# moire_v1_4-bwip.net
KiCad netlist of a schematic drawn in EAGLE
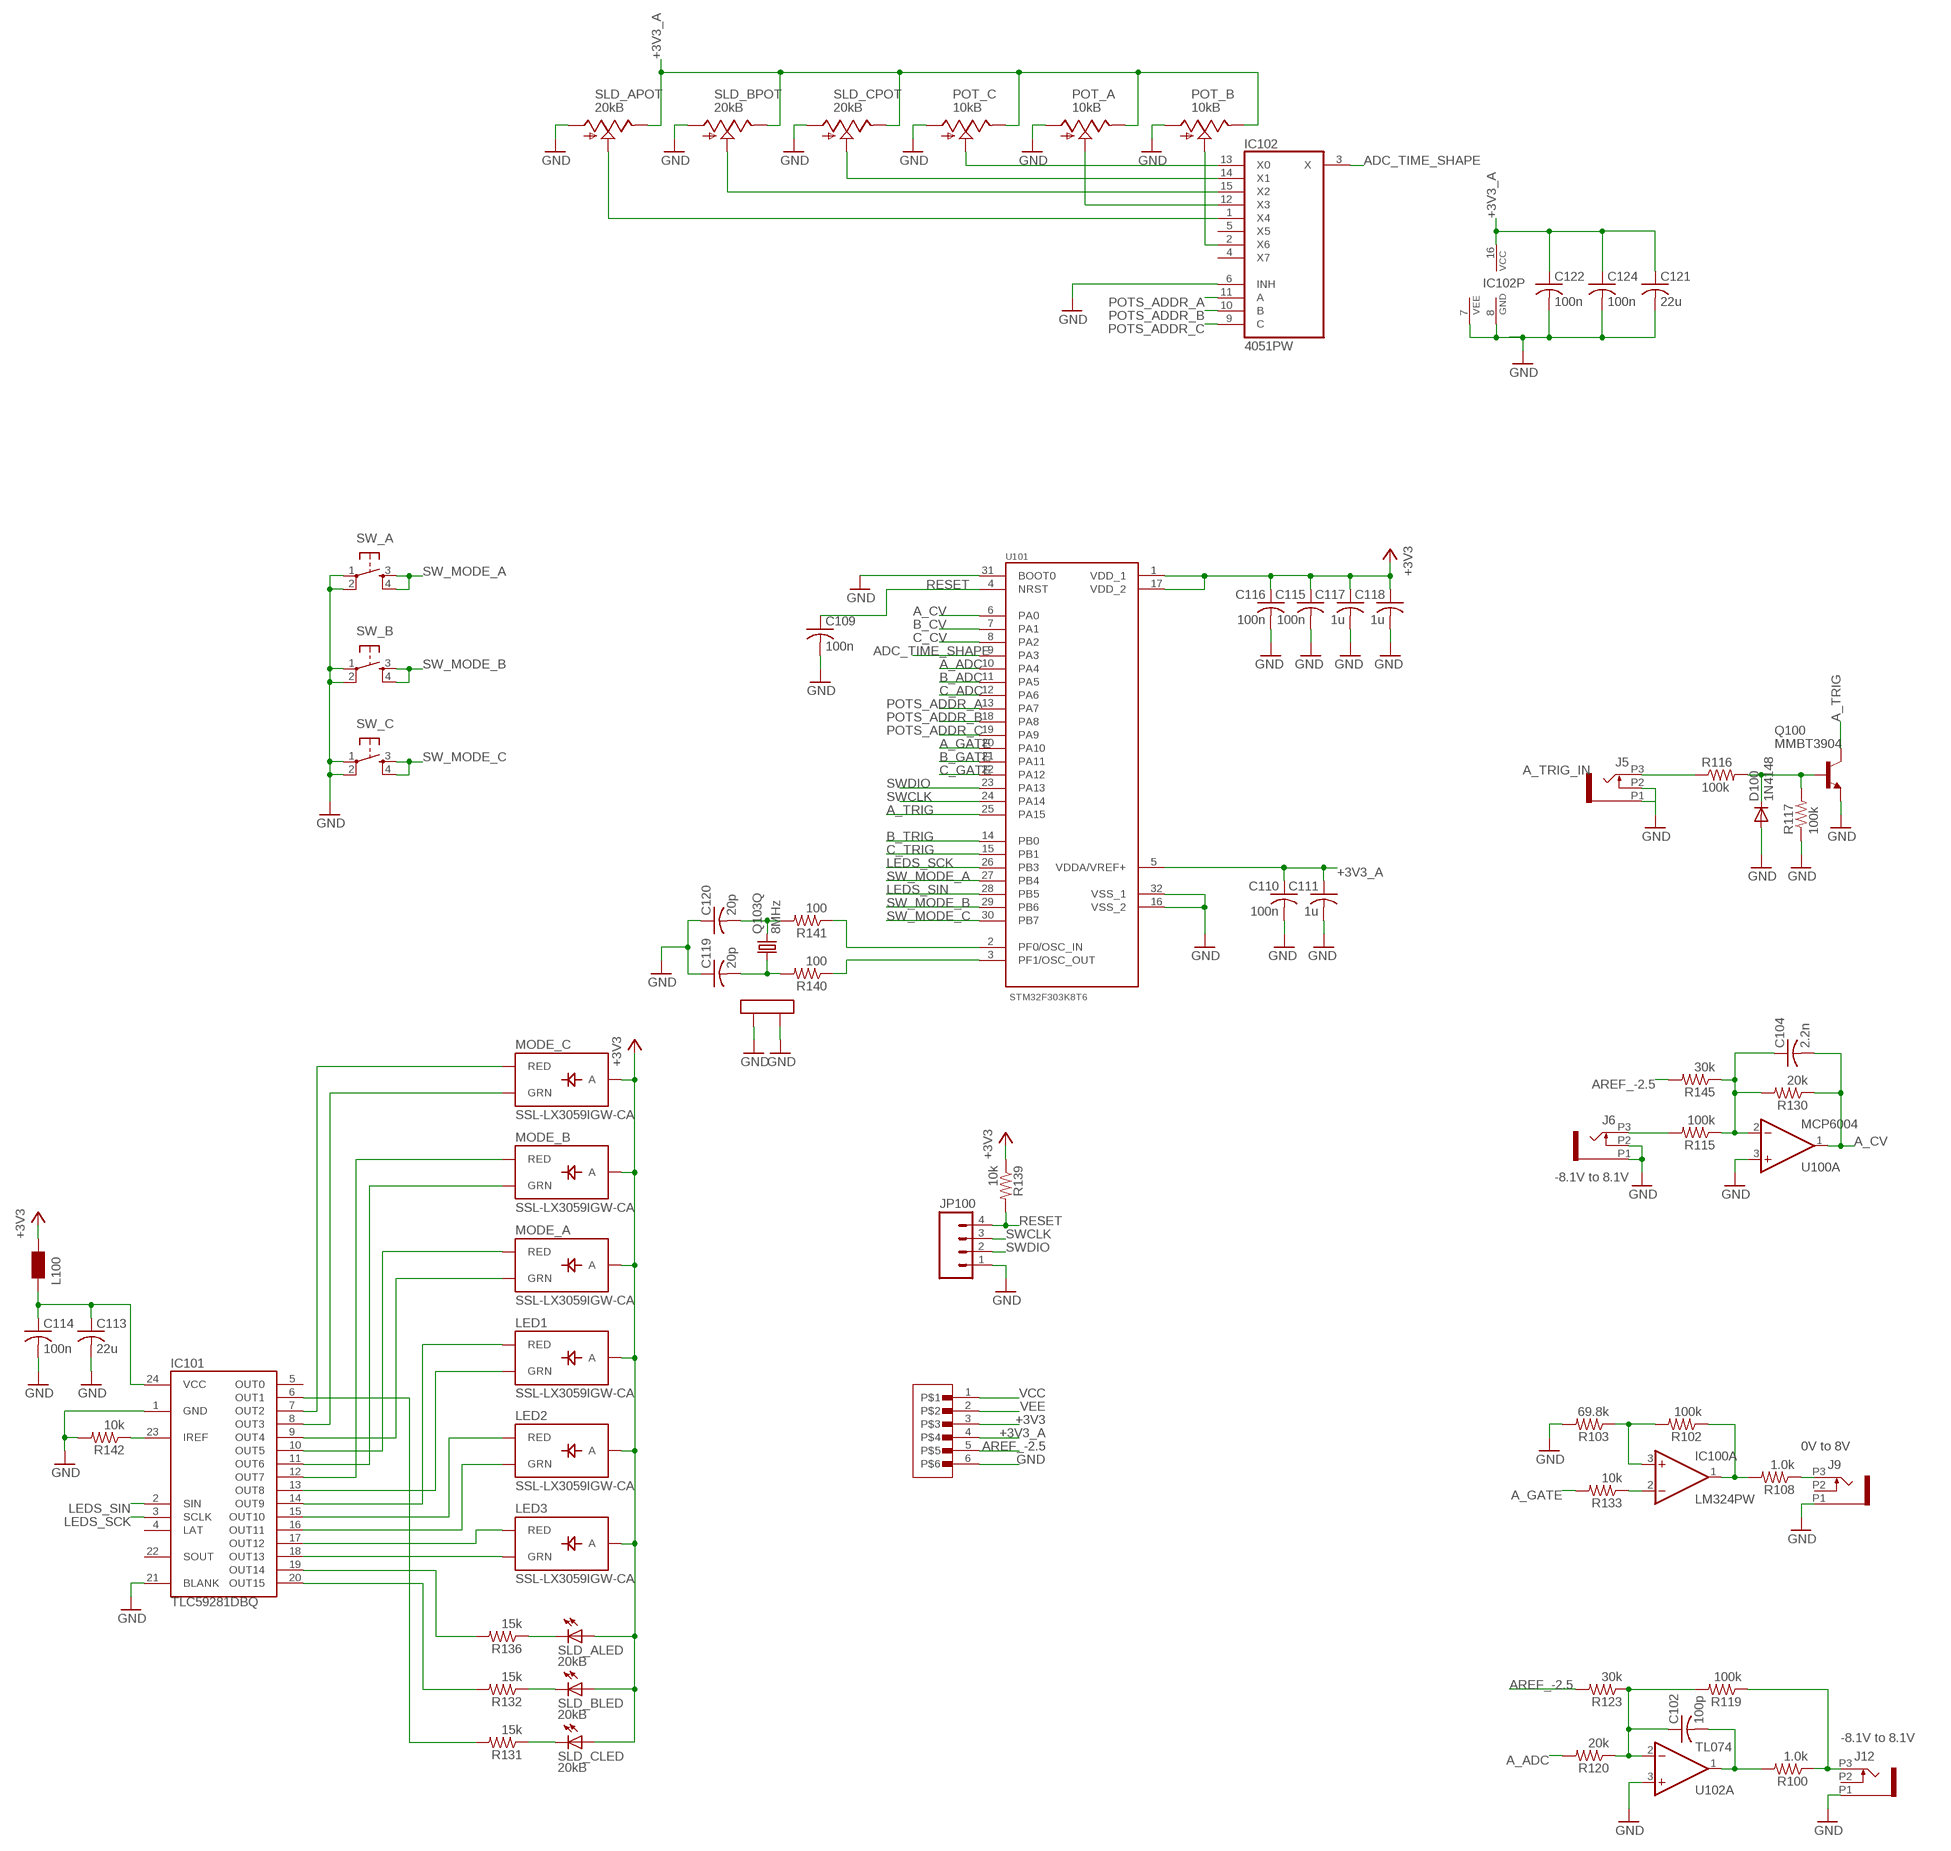
[diagram p0: schematic, sheet 1, part 1 of 2]
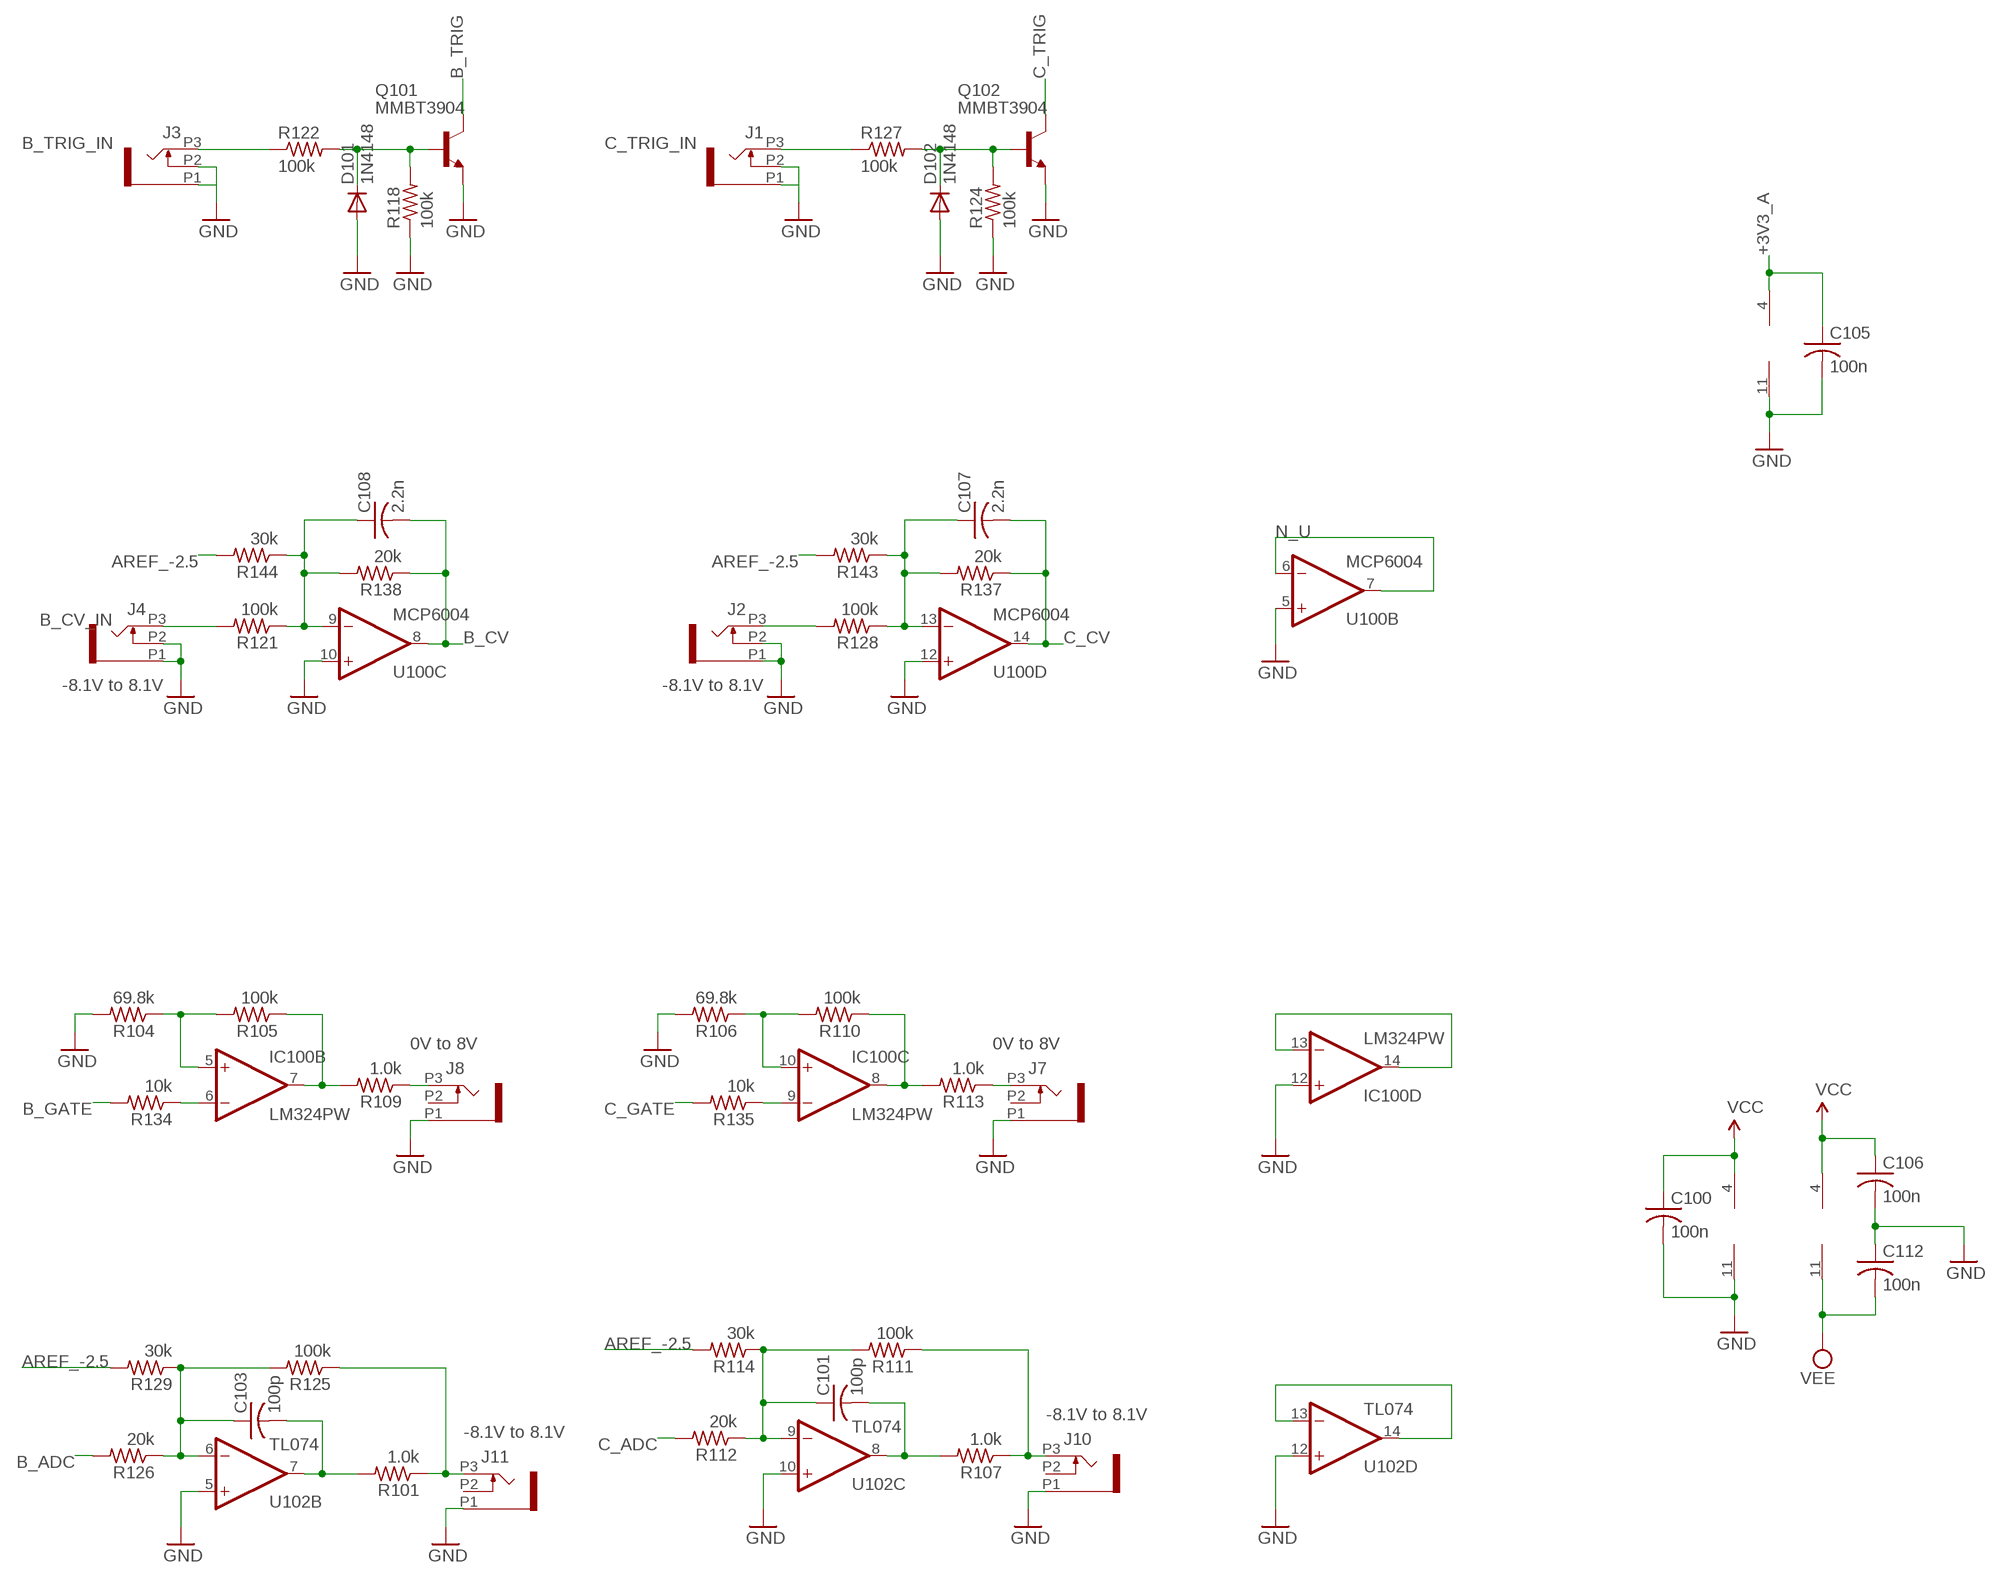
[diagram p1: schematic, sheet 1, part 2 of 2]
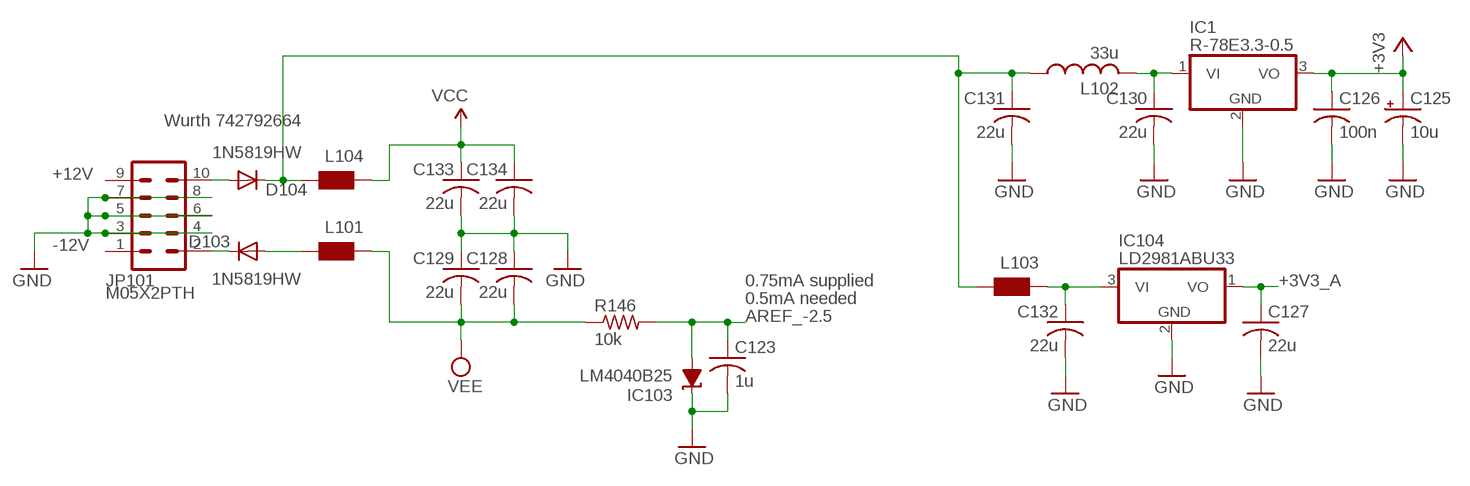
[diagram p2: schematic, sheet 2]

(export (version "E")
  (design (tool "Eeschema 10.0.6"))
  (components
    (comp (ref "C100")
      (value "100n")
      (footprint "eagle-import:C0603")
      (libsource (lib "eagle-import") (part "C-USC0603"))
    )
    (comp (ref "C101")
      (value "100p")
      (footprint "eagle-import:C0603")
      (libsource (lib "eagle-import") (part "C-USC0603"))
    )
    (comp (ref "C102")
      (value "100p")
      (footprint "eagle-import:C0603")
      (libsource (lib "eagle-import") (part "C-USC0603"))
    )
    (comp (ref "C103")
      (value "100p")
      (footprint "eagle-import:C0603")
      (libsource (lib "eagle-import") (part "C-USC0603"))
    )
    (comp (ref "C104")
      (value "2.2n")
      (footprint "eagle-import:C0603")
      (libsource (lib "eagle-import") (part "C-USC0603"))
    )
    (comp (ref "C105")
      (value "100n")
      (footprint "eagle-import:C0603")
      (libsource (lib "eagle-import") (part "C-USC0603"))
    )
    (comp (ref "C106")
      (value "100n")
      (footprint "eagle-import:C0603")
      (libsource (lib "eagle-import") (part "C-USC0603"))
    )
    (comp (ref "C107")
      (value "2.2n")
      (footprint "eagle-import:C0603")
      (libsource (lib "eagle-import") (part "C-USC0603"))
    )
    (comp (ref "C108")
      (value "2.2n")
      (footprint "eagle-import:C0603")
      (libsource (lib "eagle-import") (part "C-USC0603"))
    )
    (comp (ref "C109")
      (value "100n")
      (footprint "eagle-import:C0603")
      (libsource (lib "eagle-import") (part "C-USC0603"))
    )
    (comp (ref "C110")
      (value "100n")
      (footprint "eagle-import:C0603")
      (libsource (lib "eagle-import") (part "C-USC0603"))
    )
    (comp (ref "C111")
      (value "1u")
      (footprint "eagle-import:C0603")
      (libsource (lib "eagle-import") (part "C-USC0603"))
    )
    (comp (ref "C112")
      (value "100n")
      (footprint "eagle-import:C0603")
      (libsource (lib "eagle-import") (part "C-USC0603"))
    )
    (comp (ref "C113")
      (value "22u")
      (footprint "eagle-import:C1206")
      (libsource (lib "eagle-import") (part "C-USC1206"))
    )
    (comp (ref "C114")
      (value "100n")
      (footprint "eagle-import:C0603")
      (libsource (lib "eagle-import") (part "C-USC0603"))
    )
    (comp (ref "C115")
      (value "100n")
      (footprint "eagle-import:C0603")
      (libsource (lib "eagle-import") (part "C-USC0603"))
    )
    (comp (ref "C116")
      (value "100n")
      (footprint "eagle-import:C0603")
      (libsource (lib "eagle-import") (part "C-USC0603"))
    )
    (comp (ref "C117")
      (value "1u")
      (footprint "eagle-import:C0603")
      (libsource (lib "eagle-import") (part "C-USC0603"))
    )
    (comp (ref "C118")
      (value "1u")
      (footprint "eagle-import:C0603")
      (libsource (lib "eagle-import") (part "C-USC0603"))
    )
    (comp (ref "C119")
      (value "20p")
      (footprint "eagle-import:C0603")
      (libsource (lib "eagle-import") (part "C-USC0603"))
    )
    (comp (ref "C120")
      (value "20p")
      (footprint "eagle-import:C0603")
      (libsource (lib "eagle-import") (part "C-USC0603"))
    )
    (comp (ref "C121")
      (value "22u")
      (footprint "eagle-import:C1206")
      (libsource (lib "eagle-import") (part "C-USC1206"))
    )
    (comp (ref "C122")
      (value "100n")
      (footprint "eagle-import:C0603")
      (libsource (lib "eagle-import") (part "C-USC0603"))
    )
    (comp (ref "C124")
      (value "100n")
      (footprint "eagle-import:C0603")
      (libsource (lib "eagle-import") (part "C-USC0603"))
    )
    (comp (ref "D100")
      (value "1N4148")
      (footprint "eagle-import:SOD523")
      (libsource (lib "eagle-import") (part "DIODE-SOD523"))
    )
    (comp (ref "D101")
      (value "1N4148")
      (footprint "eagle-import:SOD523")
      (libsource (lib "eagle-import") (part "DIODE-SOD523"))
    )
    (comp (ref "D102")
      (value "1N4148")
      (footprint "eagle-import:SOD523")
      (libsource (lib "eagle-import") (part "DIODE-SOD523"))
    )
    (comp (ref "IC100")
      (value "LM324PW")
      (footprint "eagle-import:TSSOP14_065")
      (libsource (lib "eagle-import") (part "TL074PW"))
    )
    (comp (ref "IC101")
      (value "TLC59281DBQ")
      (footprint "eagle-import:TSSOP24_0635")
      (libsource (lib "eagle-import") (part "TLC59281DBQ"))
    )
    (comp (ref "IC102")
      (value "4051PW")
      (footprint "eagle-import:TSSOP16_065")
      (libsource (lib "eagle-import") (part "4051PW"))
    )
    (comp (ref "J1")
      (value "PJ301_THONKICONN6")
      (footprint "eagle-import:WQP_PJ_301M6")
      (libsource (lib "eagle-import") (part "PJ301_THONKICONN6"))
    )
    (comp (ref "J2")
      (value "PJ301_THONKICONN6")
      (footprint "eagle-import:WQP_PJ_301M6")
      (libsource (lib "eagle-import") (part "PJ301_THONKICONN6"))
    )
    (comp (ref "J3")
      (value "PJ301_THONKICONN6")
      (footprint "eagle-import:WQP_PJ_301M6")
      (libsource (lib "eagle-import") (part "PJ301_THONKICONN6"))
    )
    (comp (ref "J4")
      (value "PJ301_THONKICONN6")
      (footprint "eagle-import:WQP_PJ_301M6")
      (libsource (lib "eagle-import") (part "PJ301_THONKICONN6"))
    )
    (comp (ref "J5")
      (value "PJ301_THONKICONN6")
      (footprint "eagle-import:WQP_PJ_301M6")
      (libsource (lib "eagle-import") (part "PJ301_THONKICONN6"))
    )
    (comp (ref "J6")
      (value "PJ301_THONKICONN6")
      (footprint "eagle-import:WQP_PJ_301M6")
      (libsource (lib "eagle-import") (part "PJ301_THONKICONN6"))
    )
    (comp (ref "J7")
      (value "PJ301_THONKICONN6")
      (footprint "eagle-import:WQP_PJ_301M6")
      (libsource (lib "eagle-import") (part "PJ301_THONKICONN6"))
    )
    (comp (ref "J8")
      (value "PJ301_THONKICONN6")
      (footprint "eagle-import:WQP_PJ_301M6")
      (libsource (lib "eagle-import") (part "PJ301_THONKICONN6"))
    )
    (comp (ref "J9")
      (value "PJ301_THONKICONN6")
      (footprint "eagle-import:WQP_PJ_301M6")
      (libsource (lib "eagle-import") (part "PJ301_THONKICONN6"))
    )
    (comp (ref "J10")
      (value "PJ301_THONKICONN6")
      (footprint "eagle-import:WQP_PJ_301M6")
      (libsource (lib "eagle-import") (part "PJ301_THONKICONN6"))
    )
    (comp (ref "J11")
      (value "PJ301_THONKICONN6")
      (footprint "eagle-import:WQP_PJ_301M6")
      (libsource (lib "eagle-import") (part "PJ301_THONKICONN6"))
    )
    (comp (ref "J12")
      (value "PJ301_THONKICONN6")
      (footprint "eagle-import:WQP_PJ_301M6")
      (libsource (lib "eagle-import") (part "PJ301_THONKICONN6"))
    )
    (comp (ref "JP100")
      (value "M04PTH")
      (footprint "eagle-import:1X04")
      (libsource (lib "eagle-import") (part "M04PTH"))
    )
    (comp (ref "L100")
      (value "WE-CBF_0603")
      (footprint "eagle-import:0603")
      (libsource (lib "eagle-import") (part "WE-CBF_0603"))
    )
    (comp (ref "LED1")
      (value "SSL-LX3059IGW-CA")
      (footprint "eagle-import:LED-BICOLOR-THROUGHHOLE-LUMEX")
      (libsource (lib "eagle-import") (part "LED-BICOLOR-THROUGHHOLE-CA"))
    )
    (comp (ref "LED2")
      (value "SSL-LX3059IGW-CA")
      (footprint "eagle-import:LED-BICOLOR-THROUGHHOLE-LUMEX")
      (libsource (lib "eagle-import") (part "LED-BICOLOR-THROUGHHOLE-CA"))
    )
    (comp (ref "LED3")
      (value "SSL-LX3059IGW-CA")
      (footprint "eagle-import:LED-BICOLOR-THROUGHHOLE-LUMEX")
      (libsource (lib "eagle-import") (part "LED-BICOLOR-THROUGHHOLE-CA"))
    )
    (comp (ref "MODE_A")
      (value "SSL-LX3059IGW-CA")
      (footprint "eagle-import:LED-BICOLOR-THROUGHHOLE-LUMEX")
      (libsource (lib "eagle-import") (part "LED-BICOLOR-THROUGHHOLE-CA"))
    )
    (comp (ref "MODE_B")
      (value "SSL-LX3059IGW-CA")
      (footprint "eagle-import:LED-BICOLOR-THROUGHHOLE-LUMEX")
      (libsource (lib "eagle-import") (part "LED-BICOLOR-THROUGHHOLE-CA"))
    )
    (comp (ref "MODE_C")
      (value "SSL-LX3059IGW-CA")
      (footprint "eagle-import:LED-BICOLOR-THROUGHHOLE-LUMEX")
      (libsource (lib "eagle-import") (part "LED-BICOLOR-THROUGHHOLE-CA"))
    )
    (comp (ref "POT_A")
      (value "10kB")
      (footprint "eagle-import:ALPS_POT_VERTICAL")
      (libsource (lib "eagle-import") (part "POT_USVERTICAL"))
    )
    (comp (ref "POT_B")
      (value "10kB")
      (footprint "eagle-import:ALPS_POT_VERTICAL")
      (libsource (lib "eagle-import") (part "POT_USVERTICAL"))
    )
    (comp (ref "POT_C")
      (value "10kB")
      (footprint "eagle-import:ALPS_POT_VERTICAL")
      (libsource (lib "eagle-import") (part "POT_USVERTICAL"))
    )
    (comp (ref "Q100")
      (value "MMBT3904")
      (footprint "eagle-import:SOT23-BEC")
      (libsource (lib "eagle-import") (part "-NPN-SOT23-BECMMBT3904LT1"))
    )
    (comp (ref "Q101")
      (value "MMBT3904")
      (footprint "eagle-import:SOT23-BEC")
      (libsource (lib "eagle-import") (part "-NPN-SOT23-BECMMBT3904LT1"))
    )
    (comp (ref "Q102")
      (value "MMBT3904")
      (footprint "eagle-import:SOT23-BEC")
      (libsource (lib "eagle-import") (part "-NPN-SOT23-BECMMBT3904LT1"))
    )
    (comp (ref "Q103")
      (value "8MHz")
      (footprint "eagle-import:CTS406")
      (libsource (lib "eagle-import") (part "CRYSTAL"))
    )
    (comp (ref "R100")
      (value "1.0k")
      (footprint "eagle-import:R0603")
      (libsource (lib "eagle-import") (part "R-US_R0603"))
    )
    (comp (ref "R101")
      (value "1.0k")
      (footprint "eagle-import:R0603")
      (libsource (lib "eagle-import") (part "R-US_R0603"))
    )
    (comp (ref "R102")
      (value "100k")
      (footprint "eagle-import:R0603")
      (libsource (lib "eagle-import") (part "R-US_R0603"))
    )
    (comp (ref "R103")
      (value "69.8k")
      (footprint "eagle-import:R0603")
      (libsource (lib "eagle-import") (part "R-US_R0603"))
    )
    (comp (ref "R104")
      (value "69.8k")
      (footprint "eagle-import:R0603")
      (libsource (lib "eagle-import") (part "R-US_R0603"))
    )
    (comp (ref "R105")
      (value "100k")
      (footprint "eagle-import:R0603")
      (libsource (lib "eagle-import") (part "R-US_R0603"))
    )
    (comp (ref "R106")
      (value "69.8k")
      (footprint "eagle-import:R0603")
      (libsource (lib "eagle-import") (part "R-US_R0603"))
    )
    (comp (ref "R107")
      (value "1.0k")
      (footprint "eagle-import:R0603")
      (libsource (lib "eagle-import") (part "R-US_R0603"))
    )
    (comp (ref "R108")
      (value "1.0k")
      (footprint "eagle-import:R0603")
      (libsource (lib "eagle-import") (part "R-US_R0603"))
    )
    (comp (ref "R109")
      (value "1.0k")
      (footprint "eagle-import:R0603")
      (libsource (lib "eagle-import") (part "R-US_R0603"))
    )
    (comp (ref "R110")
      (value "100k")
      (footprint "eagle-import:R0603")
      (libsource (lib "eagle-import") (part "R-US_R0603"))
    )
    (comp (ref "R111")
      (value "100k")
      (footprint "eagle-import:R0603")
      (libsource (lib "eagle-import") (part "R-US_R0603"))
    )
    (comp (ref "R112")
      (value "20k")
      (footprint "eagle-import:R0603")
      (libsource (lib "eagle-import") (part "R-US_R0603"))
    )
    (comp (ref "R113")
      (value "1.0k")
      (footprint "eagle-import:R0603")
      (libsource (lib "eagle-import") (part "R-US_R0603"))
    )
    (comp (ref "R114")
      (value "30k")
      (footprint "eagle-import:R0603")
      (libsource (lib "eagle-import") (part "R-US_R0603"))
    )
    (comp (ref "R115")
      (value "100k")
      (footprint "eagle-import:R0603")
      (libsource (lib "eagle-import") (part "R-US_R0603"))
    )
    (comp (ref "R116")
      (value "100k")
      (footprint "eagle-import:R0603")
      (libsource (lib "eagle-import") (part "R-US_R0603"))
    )
    (comp (ref "R117")
      (value "100k")
      (footprint "eagle-import:R0603")
      (libsource (lib "eagle-import") (part "R-US_R0603"))
    )
    (comp (ref "R118")
      (value "100k")
      (footprint "eagle-import:R0603")
      (libsource (lib "eagle-import") (part "R-US_R0603"))
    )
    (comp (ref "R119")
      (value "100k")
      (footprint "eagle-import:R0603")
      (libsource (lib "eagle-import") (part "R-US_R0603"))
    )
    (comp (ref "R120")
      (value "20k")
      (footprint "eagle-import:R0603")
      (libsource (lib "eagle-import") (part "R-US_R0603"))
    )
    (comp (ref "R121")
      (value "100k")
      (footprint "eagle-import:R0603")
      (libsource (lib "eagle-import") (part "R-US_R0603"))
    )
    (comp (ref "R122")
      (value "100k")
      (footprint "eagle-import:R0603")
      (libsource (lib "eagle-import") (part "R-US_R0603"))
    )
    (comp (ref "R123")
      (value "30k")
      (footprint "eagle-import:R0603")
      (libsource (lib "eagle-import") (part "R-US_R0603"))
    )
    (comp (ref "R124")
      (value "100k")
      (footprint "eagle-import:R0603")
      (libsource (lib "eagle-import") (part "R-US_R0603"))
    )
    (comp (ref "R125")
      (value "100k")
      (footprint "eagle-import:R0603")
      (libsource (lib "eagle-import") (part "R-US_R0603"))
    )
    (comp (ref "R126")
      (value "20k")
      (footprint "eagle-import:R0603")
      (libsource (lib "eagle-import") (part "R-US_R0603"))
    )
    (comp (ref "R127")
      (value "100k")
      (footprint "eagle-import:R0603")
      (libsource (lib "eagle-import") (part "R-US_R0603"))
    )
    (comp (ref "R128")
      (value "100k")
      (footprint "eagle-import:R0603")
      (libsource (lib "eagle-import") (part "R-US_R0603"))
    )
    (comp (ref "R129")
      (value "30k")
      (footprint "eagle-import:R0603")
      (libsource (lib "eagle-import") (part "R-US_R0603"))
    )
    (comp (ref "R130")
      (value "20k")
      (footprint "eagle-import:R0603")
      (libsource (lib "eagle-import") (part "R-US_R0603"))
    )
    (comp (ref "R131")
      (value "15k")
      (footprint "eagle-import:R0603")
      (libsource (lib "eagle-import") (part "R-US_R0603"))
    )
    (comp (ref "R132")
      (value "15k")
      (footprint "eagle-import:R0603")
      (libsource (lib "eagle-import") (part "R-US_R0603"))
    )
    (comp (ref "R133")
      (value "10k")
      (footprint "eagle-import:R0603")
      (libsource (lib "eagle-import") (part "R-US_R0603"))
    )
    (comp (ref "R134")
      (value "10k")
      (footprint "eagle-import:R0603")
      (libsource (lib "eagle-import") (part "R-US_R0603"))
    )
    (comp (ref "R135")
      (value "10k")
      (footprint "eagle-import:R0603")
      (libsource (lib "eagle-import") (part "R-US_R0603"))
    )
    (comp (ref "R136")
      (value "15k")
      (footprint "eagle-import:R0603")
      (libsource (lib "eagle-import") (part "R-US_R0603"))
    )
    (comp (ref "R137")
      (value "20k")
      (footprint "eagle-import:R0603")
      (libsource (lib "eagle-import") (part "R-US_R0603"))
    )
    (comp (ref "R138")
      (value "20k")
      (footprint "eagle-import:R0603")
      (libsource (lib "eagle-import") (part "R-US_R0603"))
    )
    (comp (ref "R139")
      (value "10k")
      (footprint "eagle-import:R0603")
      (libsource (lib "eagle-import") (part "R-US_R0603"))
    )
    (comp (ref "R140")
      (value "100")
      (footprint "eagle-import:R0603")
      (libsource (lib "eagle-import") (part "R-US_R0603"))
    )
    (comp (ref "R141")
      (value "100")
      (footprint "eagle-import:R0603")
      (libsource (lib "eagle-import") (part "R-US_R0603"))
    )
    (comp (ref "R142")
      (value "10k")
      (footprint "eagle-import:R0603")
      (libsource (lib "eagle-import") (part "R-US_R0603"))
    )
    (comp (ref "R143")
      (value "30k")
      (footprint "eagle-import:R0603")
      (libsource (lib "eagle-import") (part "R-US_R0603"))
    )
    (comp (ref "R144")
      (value "30k")
      (footprint "eagle-import:R0603")
      (libsource (lib "eagle-import") (part "R-US_R0603"))
    )
    (comp (ref "R145")
      (value "30k")
      (footprint "eagle-import:R0603")
      (libsource (lib "eagle-import") (part "R-US_R0603"))
    )
    (comp (ref "SLD_A")
      (value "20kB")
      (footprint "eagle-import:BOURNS_SLIDER")
      (libsource (lib "eagle-import") (part "BOURNS_SLIDER"))
    )
    (comp (ref "SLD_B")
      (value "20kB")
      (footprint "eagle-import:BOURNS_SLIDER")
      (libsource (lib "eagle-import") (part "BOURNS_SLIDER"))
    )
    (comp (ref "SLD_C")
      (value "20kB")
      (footprint "eagle-import:BOURNS_SLIDER")
      (libsource (lib "eagle-import") (part "BOURNS_SLIDER"))
    )
    (comp (ref "SW_A")
      (value "TAC_SWITCHPTH")
      (footprint "eagle-import:TACTILE-PTH")
      (libsource (lib "eagle-import") (part "TAC_SWITCHPTH"))
    )
    (comp (ref "SW_B")
      (value "TAC_SWITCHPTH")
      (footprint "eagle-import:TACTILE-PTH")
      (libsource (lib "eagle-import") (part "TAC_SWITCHPTH"))
    )
    (comp (ref "SW_C")
      (value "TAC_SWITCHPTH")
      (footprint "eagle-import:TACTILE-PTH")
      (libsource (lib "eagle-import") (part "TAC_SWITCHPTH"))
    )
    (comp (ref "U$1")
      (value "1X6-SMD-TESTPAD")
      (footprint "eagle-import:6X1-SMD-TESTPAD")
      (libsource (lib "eagle-import") (part "1X6-SMD-TESTPAD"))
    )
    (comp (ref "U100")
      (value "MCP6004")
      (footprint "eagle-import:SO14")
      (libsource (lib "eagle-import") (part "MCP6004_SMD"))
    )
    (comp (ref "U101")
      (value "STM32F303K8T6")
      (footprint "eagle-import:QFP80P900X900X160-32N")
      (fields (field (name "MF") "STMicroelectronics"))
      (libsource (lib "eagle-import") (part "STM32F303K8T6"))
    )
    (comp (ref "U102")
      (value "TL074")
      (footprint "eagle-import:SO14")
      (libsource (lib "eagle-import") (part "TL074_SMD"))
    )
    (comp (ref "C123")
      (value "1u")
      (footprint "eagle-import:C0603")
      (libsource (lib "eagle-import") (part "C-USC0603"))
    )
    (comp (ref "C125")
      (value "10u")
      (footprint "eagle-import:PANASONIC_A")
      (libsource (lib "eagle-import") (part "CPOL-USA"))
    )
    (comp (ref "C126")
      (value "100n")
      (footprint "eagle-import:C0603")
      (libsource (lib "eagle-import") (part "C-USC0603"))
    )
    (comp (ref "C127")
      (value "22u")
      (footprint "eagle-import:C1206")
      (libsource (lib "eagle-import") (part "C-USC1206"))
    )
    (comp (ref "C128")
      (value "22u")
      (footprint "eagle-import:C1206")
      (libsource (lib "eagle-import") (part "C-USC1206"))
    )
    (comp (ref "C129")
      (value "22u")
      (footprint "eagle-import:C1206")
      (libsource (lib "eagle-import") (part "C-USC1206"))
    )
    (comp (ref "C130")
      (value "22u")
      (footprint "eagle-import:C1206")
      (libsource (lib "eagle-import") (part "C-USC1206"))
    )
    (comp (ref "C131")
      (value "22u")
      (footprint "eagle-import:C1206")
      (libsource (lib "eagle-import") (part "C-USC1206"))
    )
    (comp (ref "C132")
      (value "22u")
      (footprint "eagle-import:C1206")
      (libsource (lib "eagle-import") (part "C-USC1206"))
    )
    (comp (ref "C133")
      (value "22u")
      (footprint "eagle-import:C1206")
      (libsource (lib "eagle-import") (part "C-USC1206"))
    )
    (comp (ref "C134")
      (value "22u")
      (footprint "eagle-import:C1206")
      (libsource (lib "eagle-import") (part "C-USC1206"))
    )
    (comp (ref "D103")
      (value "1N5819HW")
      (footprint "eagle-import:SOD123")
      (libsource (lib "eagle-import") (part "DIODE-SOD123"))
    )
    (comp (ref "D104")
      (value "1N5819HW")
      (footprint "eagle-import:SOD123")
      (libsource (lib "eagle-import") (part "DIODE-SOD123"))
    )
    (comp (ref "IC1")
      (value "R-78E3.3-0.5")
      (footprint "eagle-import:WE78")
      (libsource (lib "eagle-import") (part "WE173950378"))
    )
    (comp (ref "IC103")
      (value "LM4040B25")
      (footprint "eagle-import:DBZ_R-PDSO-G3")
      (libsource (lib "eagle-import") (part "LM4041DBZB12"))
    )
    (comp (ref "IC104")
      (value "LD2981ABU33")
      (footprint "eagle-import:SOT89")
      (libsource (lib "eagle-import") (part "LD2981ABU"))
    )
    (comp (ref "JP101")
      (value "M05X2PTH")
      (footprint "eagle-import:2X5-PTH")
      (libsource (lib "eagle-import") (part "M05X2PTH"))
    )
    (comp (ref "L101")
      (value "WE-CBF_0603")
      (footprint "eagle-import:0603")
      (libsource (lib "eagle-import") (part "WE-CBF_0603"))
    )
    (comp (ref "L102")
      (value "33u")
      (footprint "eagle-import:L2012C")
      (libsource (lib "eagle-import") (part "L-USL2012C"))
    )
    (comp (ref "L103")
      (value "WE-CBF_0603")
      (footprint "eagle-import:0603")
      (libsource (lib "eagle-import") (part "WE-CBF_0603"))
    )
    (comp (ref "L104")
      (value "WE-CBF_0603")
      (footprint "eagle-import:0603")
      (libsource (lib "eagle-import") (part "WE-CBF_0603"))
    )
    (comp (ref "R146")
      (value "10k")
      (footprint "eagle-import:R0603")
      (libsource (lib "eagle-import") (part "R-US_R0603"))
    )
  )
  (nets
    (net (code "1") (name "+3V3") (class "Default")
      (node (ref "C115") (pin "1") (pinfunction "1_1") (pintype "passive"))
      (node (ref "C116") (pin "1") (pinfunction "1_1") (pintype "passive"))
      (node (ref "C117") (pin "1") (pinfunction "1_1") (pintype "passive"))
      (node (ref "C118") (pin "1") (pinfunction "1_1") (pintype "passive"))
      (node (ref "C125") (pin "+") (pinfunction "+_+") (pintype "passive"))
      (node (ref "C126") (pin "1") (pinfunction "1_1") (pintype "passive"))
      (node (ref "IC1") (pin "3") (pinfunction "VO_3") (pintype "passive"))
      (node (ref "L100") (pin "2") (pinfunction "2_2") (pintype "passive"))
      (node (ref "LED1") (pin "A") (pinfunction "A_A") (pintype "bidirectional"))
      (node (ref "LED2") (pin "A") (pinfunction "A_A") (pintype "bidirectional"))
      (node (ref "LED3") (pin "A") (pinfunction "A_A") (pintype "bidirectional"))
      (node (ref "MODE_A") (pin "A") (pinfunction "A_A") (pintype "bidirectional"))
      (node (ref "MODE_B") (pin "A") (pinfunction "A_A") (pintype "bidirectional"))
      (node (ref "MODE_C") (pin "A") (pinfunction "A_A") (pintype "bidirectional"))
      (node (ref "R139") (pin "1") (pinfunction "1_1") (pintype "passive"))
      (node (ref "SLD_A") (pin "B") (pinfunction "A_B") (pintype "passive"))
      (node (ref "SLD_B") (pin "B") (pinfunction "A_B") (pintype "passive"))
      (node (ref "SLD_C") (pin "B") (pinfunction "A_B") (pintype "passive"))
      (node (ref "U$1") (pin "3") (pinfunction "P$3_3") (pintype "bidirectional"))
      (node (ref "U101") (pin "1") (pinfunction "VDD_1_1") (pintype "power_in"))
      (node (ref "U101") (pin "17") (pinfunction "VDD_2_17") (pintype "power_in"))
    )
    (net (code "2") (name "+3V3_A") (class "Default")
      (node (ref "C105") (pin "1") (pinfunction "1_1") (pintype "passive"))
      (node (ref "C110") (pin "1") (pinfunction "1_1") (pintype "passive"))
      (node (ref "C111") (pin "1") (pinfunction "1_1") (pintype "passive"))
      (node (ref "C121") (pin "1") (pinfunction "1_1") (pintype "passive"))
      (node (ref "C122") (pin "1") (pinfunction "1_1") (pintype "passive"))
      (node (ref "C124") (pin "1") (pinfunction "1_1") (pintype "passive"))
      (node (ref "C127") (pin "1") (pinfunction "1_1") (pintype "passive"))
      (node (ref "IC102") (pin "16") (pinfunction "VCC_16") (pintype "power_in"))
      (node (ref "IC104") (pin "1") (pinfunction "VO_1") (pintype "passive"))
      (node (ref "POT_A") (pin "P$1") (pinfunction "E_P$1") (pintype "passive"))
      (node (ref "POT_B") (pin "P$1") (pinfunction "E_P$1") (pintype "passive"))
      (node (ref "POT_C") (pin "P$1") (pinfunction "E_P$1") (pintype "passive"))
      (node (ref "SLD_A") (pin "3") (pinfunction "E_3") (pintype "passive"))
      (node (ref "SLD_B") (pin "3") (pinfunction "E_3") (pintype "passive"))
      (node (ref "SLD_C") (pin "3") (pinfunction "E_3") (pintype "passive"))
      (node (ref "U$1") (pin "4") (pinfunction "P$4_4") (pintype "bidirectional"))
      (node (ref "U100") (pin "4") (pinfunction "V+_4") (pintype "power_in"))
      (node (ref "U101") (pin "5") (pinfunction "VDDA/VREF+_5") (pintype "power_in"))
    )
    (net (code "3") (name "+12V") (class "Default")
      (node (ref "D104") (pin "A") (pinfunction "A_A") (pintype "passive"))
      (node (ref "JP101") (pin "10") (pinfunction "10_10") (pintype "passive"))
      (node (ref "JP101") (pin "9") (pinfunction "9_9") (pintype "passive"))
    )
    (net (code "4") (name "-12V") (class "Default")
      (node (ref "D103") (pin "C") (pinfunction "C_C") (pintype "passive"))
      (node (ref "JP101") (pin "1") (pinfunction "1_1") (pintype "passive"))
      (node (ref "JP101") (pin "2") (pinfunction "2_2") (pintype "passive"))
    )
    (net (code "5") (name "ADC_TIME_SHAPE") (class "Default")
      (node (ref "IC102") (pin "3") (pinfunction "X_3") (pintype "bidirectional"))
      (node (ref "U101") (pin "9") (pinfunction "PA3_9") (pintype "bidirectional"))
    )
    (net (code "6") (name "AREF_-2.5") (class "Default")
      (node (ref "C123") (pin "1") (pinfunction "1_1") (pintype "passive"))
      (node (ref "IC103") (pin "2") (pinfunction "A_2") (pintype "passive"))
      (node (ref "R114") (pin "2") (pinfunction "2_2") (pintype "passive"))
      (node (ref "R123") (pin "2") (pinfunction "2_2") (pintype "passive"))
      (node (ref "R129") (pin "2") (pinfunction "2_2") (pintype "passive"))
      (node (ref "R143") (pin "2") (pinfunction "2_2") (pintype "passive"))
      (node (ref "R144") (pin "2") (pinfunction "2_2") (pintype "passive"))
      (node (ref "R145") (pin "2") (pinfunction "2_2") (pintype "passive"))
      (node (ref "R146") (pin "2") (pinfunction "2_2") (pintype "passive"))
      (node (ref "U$1") (pin "5") (pinfunction "P$5_5") (pintype "bidirectional"))
    )
    (net (code "7") (name "A_ADC") (class "Default")
      (node (ref "R120") (pin "2") (pinfunction "2_2") (pintype "passive"))
      (node (ref "U101") (pin "10") (pinfunction "PA4_10") (pintype "bidirectional"))
    )
    (net (code "8") (name "A_CV") (class "Default")
      (node (ref "C104") (pin "2") (pinfunction "2_2") (pintype "passive"))
      (node (ref "R130") (pin "1") (pinfunction "1_1") (pintype "passive"))
      (node (ref "U100") (pin "1") (pinfunction "OUT_1") (pintype "output"))
      (node (ref "U101") (pin "6") (pinfunction "PA0_6") (pintype "bidirectional"))
    )
    (net (code "9") (name "A_GATE") (class "Default")
      (node (ref "R133") (pin "2") (pinfunction "2_2") (pintype "passive"))
      (node (ref "U101") (pin "20") (pinfunction "PA10_20") (pintype "bidirectional"))
    )
    (net (code "10") (name "A_TRIG") (class "Default")
      (node (ref "Q100") (pin "C") (pinfunction "C_C") (pintype "passive"))
      (node (ref "U101") (pin "25") (pinfunction "PA15_25") (pintype "bidirectional"))
    )
    (net (code "11") (name "A_TRIG_IN") (class "Default")
      (node (ref "J5") (pin "P3") (pinfunction "3_P3") (pintype "passive"))
      (node (ref "R116") (pin "1") (pinfunction "1_1") (pintype "passive"))
    )
    (net (code "12") (name "B_ADC") (class "Default")
      (node (ref "R126") (pin "2") (pinfunction "2_2") (pintype "passive"))
      (node (ref "U101") (pin "11") (pinfunction "PA5_11") (pintype "bidirectional"))
    )
    (net (code "13") (name "B_CV") (class "Default")
      (node (ref "C108") (pin "2") (pinfunction "2_2") (pintype "passive"))
      (node (ref "R138") (pin "1") (pinfunction "1_1") (pintype "passive"))
      (node (ref "U100") (pin "8") (pinfunction "OUT_8") (pintype "output"))
      (node (ref "U101") (pin "7") (pinfunction "PA1_7") (pintype "bidirectional"))
    )
    (net (code "14") (name "B_CV_IN") (class "Default")
      (node (ref "J4") (pin "P3") (pinfunction "3_P3") (pintype "passive"))
      (node (ref "R121") (pin "2") (pinfunction "2_2") (pintype "passive"))
    )
    (net (code "15") (name "B_GATE") (class "Default")
      (node (ref "R134") (pin "2") (pinfunction "2_2") (pintype "passive"))
      (node (ref "U101") (pin "21") (pinfunction "PA11_21") (pintype "bidirectional"))
    )
    (net (code "16") (name "B_TRIG") (class "Default")
      (node (ref "Q101") (pin "C") (pinfunction "C_C") (pintype "passive"))
      (node (ref "U101") (pin "14") (pinfunction "PB0_14") (pintype "bidirectional"))
    )
    (net (code "17") (name "B_TRIG_IN") (class "Default")
      (node (ref "J3") (pin "P3") (pinfunction "3_P3") (pintype "passive"))
      (node (ref "R122") (pin "1") (pinfunction "1_1") (pintype "passive"))
    )
    (net (code "18") (name "C_ADC") (class "Default")
      (node (ref "R112") (pin "2") (pinfunction "2_2") (pintype "passive"))
      (node (ref "U101") (pin "12") (pinfunction "PA6_12") (pintype "bidirectional"))
    )
    (net (code "19") (name "C_CV") (class "Default")
      (node (ref "C107") (pin "2") (pinfunction "2_2") (pintype "passive"))
      (node (ref "R137") (pin "1") (pinfunction "1_1") (pintype "passive"))
      (node (ref "U100") (pin "14") (pinfunction "OUT_14") (pintype "output"))
      (node (ref "U101") (pin "8") (pinfunction "PA2_8") (pintype "bidirectional"))
    )
    (net (code "20") (name "C_GATE") (class "Default")
      (node (ref "R135") (pin "2") (pinfunction "2_2") (pintype "passive"))
      (node (ref "U101") (pin "22") (pinfunction "PA12_22") (pintype "bidirectional"))
    )
    (net (code "21") (name "C_TRIG") (class "Default")
      (node (ref "Q102") (pin "C") (pinfunction "C_C") (pintype "passive"))
      (node (ref "U101") (pin "15") (pinfunction "PB1_15") (pintype "bidirectional"))
    )
    (net (code "22") (name "C_TRIG_IN") (class "Default")
      (node (ref "J1") (pin "P3") (pinfunction "3_P3") (pintype "passive"))
      (node (ref "R127") (pin "1") (pinfunction "1_1") (pintype "passive"))
    )
    (net (code "23") (name "GND") (class "Default")
      (node (ref "C100") (pin "2") (pinfunction "2_2") (pintype "passive"))
      (node (ref "C105") (pin "2") (pinfunction "2_2") (pintype "passive"))
      (node (ref "C106") (pin "2") (pinfunction "2_2") (pintype "passive"))
      (node (ref "C109") (pin "2") (pinfunction "2_2") (pintype "passive"))
      (node (ref "C110") (pin "2") (pinfunction "2_2") (pintype "passive"))
      (node (ref "C111") (pin "2") (pinfunction "2_2") (pintype "passive"))
      (node (ref "C112") (pin "1") (pinfunction "1_1") (pintype "passive"))
      (node (ref "C113") (pin "2") (pinfunction "2_2") (pintype "passive"))
      (node (ref "C114") (pin "2") (pinfunction "2_2") (pintype "passive"))
      (node (ref "C115") (pin "2") (pinfunction "2_2") (pintype "passive"))
      (node (ref "C116") (pin "2") (pinfunction "2_2") (pintype "passive"))
      (node (ref "C117") (pin "2") (pinfunction "2_2") (pintype "passive"))
      (node (ref "C118") (pin "2") (pinfunction "2_2") (pintype "passive"))
      (node (ref "C119") (pin "1") (pinfunction "1_1") (pintype "passive"))
      (node (ref "C120") (pin "1") (pinfunction "1_1") (pintype "passive"))
      (node (ref "C121") (pin "2") (pinfunction "2_2") (pintype "passive"))
      (node (ref "C122") (pin "2") (pinfunction "2_2") (pintype "passive"))
      (node (ref "C123") (pin "2") (pinfunction "2_2") (pintype "passive"))
      (node (ref "C124") (pin "2") (pinfunction "2_2") (pintype "passive"))
      (node (ref "C125") (pin "-") (pinfunction "-_-") (pintype "passive"))
      (node (ref "C126") (pin "2") (pinfunction "2_2") (pintype "passive"))
      (node (ref "C127") (pin "2") (pinfunction "2_2") (pintype "passive"))
      (node (ref "C128") (pin "1") (pinfunction "1_1") (pintype "passive"))
      (node (ref "C129") (pin "1") (pinfunction "1_1") (pintype "passive"))
      (node (ref "C130") (pin "2") (pinfunction "2_2") (pintype "passive"))
      (node (ref "C131") (pin "2") (pinfunction "2_2") (pintype "passive"))
      (node (ref "C132") (pin "2") (pinfunction "2_2") (pintype "passive"))
      (node (ref "C133") (pin "2") (pinfunction "2_2") (pintype "passive"))
      (node (ref "C134") (pin "2") (pinfunction "2_2") (pintype "passive"))
      (node (ref "D100") (pin "A") (pinfunction "A_A") (pintype "passive"))
      (node (ref "D101") (pin "A") (pinfunction "A_A") (pintype "passive"))
      (node (ref "D102") (pin "A") (pinfunction "A_A") (pintype "passive"))
      (node (ref "IC1") (pin "2") (pinfunction "GND_2") (pintype "passive"))
      (node (ref "IC100") (pin "11") (pinfunction "V-_11") (pintype "power_in"))
      (node (ref "IC100") (pin "12") (pinfunction "+IN_12") (pintype "input"))
      (node (ref "IC101") (pin "1") (pinfunction "GND_1") (pintype "bidirectional"))
      (node (ref "IC101") (pin "21") (pinfunction "BLANK_21") (pintype "bidirectional"))
      (node (ref "IC102") (pin "6") (pinfunction "INH_6") (pintype "input"))
      (node (ref "IC102") (pin "7") (pinfunction "VEE_7") (pintype "power_in"))
      (node (ref "IC102") (pin "8") (pinfunction "GND_8") (pintype "power_in"))
      (node (ref "IC103") (pin "1") (pinfunction "C_1") (pintype "passive"))
      (node (ref "IC104") (pin "2") (pinfunction "GND_2") (pintype "passive"))
      (node (ref "J1") (pin "P1") (pinfunction "1_P1") (pintype "passive"))
      (node (ref "J1") (pin "P2") (pinfunction "2_P2") (pintype "passive"))
      (node (ref "J10") (pin "P1") (pinfunction "1_P1") (pintype "passive"))
      (node (ref "J11") (pin "P1") (pinfunction "1_P1") (pintype "passive"))
      (node (ref "J12") (pin "P1") (pinfunction "1_P1") (pintype "passive"))
      (node (ref "J2") (pin "P1") (pinfunction "1_P1") (pintype "passive"))
      (node (ref "J2") (pin "P2") (pinfunction "2_P2") (pintype "passive"))
      (node (ref "J3") (pin "P1") (pinfunction "1_P1") (pintype "passive"))
      (node (ref "J3") (pin "P2") (pinfunction "2_P2") (pintype "passive"))
      (node (ref "J4") (pin "P1") (pinfunction "1_P1") (pintype "passive"))
      (node (ref "J4") (pin "P2") (pinfunction "2_P2") (pintype "passive"))
      (node (ref "J5") (pin "P1") (pinfunction "1_P1") (pintype "passive"))
      (node (ref "J5") (pin "P2") (pinfunction "2_P2") (pintype "passive"))
      (node (ref "J6") (pin "P1") (pinfunction "1_P1") (pintype "passive"))
      (node (ref "J6") (pin "P2") (pinfunction "2_P2") (pintype "passive"))
      (node (ref "J7") (pin "P1") (pinfunction "1_P1") (pintype "passive"))
      (node (ref "J8") (pin "P1") (pinfunction "1_P1") (pintype "passive"))
      (node (ref "J9") (pin "P1") (pinfunction "1_P1") (pintype "passive"))
      (node (ref "JP100") (pin "1") (pinfunction "1_1") (pintype "passive"))
      (node (ref "JP101") (pin "3") (pinfunction "3_3") (pintype "passive"))
      (node (ref "JP101") (pin "4") (pinfunction "4_4") (pintype "passive"))
      (node (ref "JP101") (pin "5") (pinfunction "5_5") (pintype "passive"))
      (node (ref "JP101") (pin "6") (pinfunction "6_6") (pintype "passive"))
      (node (ref "JP101") (pin "7") (pinfunction "7_7") (pintype "passive"))
      (node (ref "JP101") (pin "8") (pinfunction "8_8") (pintype "passive"))
      (node (ref "POT_A") (pin "P$3") (pinfunction "A_P$3") (pintype "passive"))
      (node (ref "POT_B") (pin "P$3") (pinfunction "A_P$3") (pintype "passive"))
      (node (ref "POT_C") (pin "P$3") (pinfunction "A_P$3") (pintype "passive"))
      (node (ref "Q100") (pin "E") (pinfunction "E_E") (pintype "passive"))
      (node (ref "Q101") (pin "E") (pinfunction "E_E") (pintype "passive"))
      (node (ref "Q102") (pin "E") (pinfunction "E_E") (pintype "passive"))
      (node (ref "Q103") (pin "2") (pinfunction "LID1_2") (pintype "power_in"))
      (node (ref "Q103") (pin "4") (pinfunction "LID2_4") (pintype "power_in"))
      (node (ref "R103") (pin "2") (pinfunction "2_2") (pintype "passive"))
      (node (ref "R104") (pin "2") (pinfunction "2_2") (pintype "passive"))
      (node (ref "R106") (pin "2") (pinfunction "2_2") (pintype "passive"))
      (node (ref "R117") (pin "1") (pinfunction "1_1") (pintype "passive"))
      (node (ref "R118") (pin "1") (pinfunction "1_1") (pintype "passive"))
      (node (ref "R124") (pin "1") (pinfunction "1_1") (pintype "passive"))
      (node (ref "R142") (pin "2") (pinfunction "2_2") (pintype "passive"))
      (node (ref "SLD_A") (pin "1") (pinfunction "A_1") (pintype "passive"))
      (node (ref "SLD_B") (pin "1") (pinfunction "A_1") (pintype "passive"))
      (node (ref "SLD_C") (pin "1") (pinfunction "A_1") (pintype "passive"))
      (node (ref "SW_A") (pin "1") (pinfunction "1_1") (pintype "passive"))
      (node (ref "SW_A") (pin "2") (pinfunction "2_2") (pintype "passive"))
      (node (ref "SW_B") (pin "1") (pinfunction "1_1") (pintype "passive"))
      (node (ref "SW_B") (pin "2") (pinfunction "2_2") (pintype "passive"))
      (node (ref "SW_C") (pin "1") (pinfunction "1_1") (pintype "passive"))
      (node (ref "SW_C") (pin "2") (pinfunction "2_2") (pintype "passive"))
      (node (ref "U$1") (pin "6") (pinfunction "P$6_6") (pintype "bidirectional"))
      (node (ref "U100") (pin "10") (pinfunction "+IN_10") (pintype "input"))
      (node (ref "U100") (pin "11") (pinfunction "V-_11") (pintype "power_in"))
      (node (ref "U100") (pin "12") (pinfunction "+IN_12") (pintype "input"))
      (node (ref "U100") (pin "3") (pinfunction "+IN_3") (pintype "input"))
      (node (ref "U100") (pin "5") (pinfunction "+IN_5") (pintype "input"))
      (node (ref "U101") (pin "16") (pinfunction "VSS_2_16") (pintype "power_in"))
      (node (ref "U101") (pin "31") (pinfunction "BOOT0_31") (pintype "input"))
      (node (ref "U101") (pin "32") (pinfunction "VSS_1_32") (pintype "power_in"))
      (node (ref "U102") (pin "10") (pinfunction "+IN_10") (pintype "input"))
      (node (ref "U102") (pin "12") (pinfunction "+IN_12") (pintype "input"))
      (node (ref "U102") (pin "3") (pinfunction "+IN_3") (pintype "input"))
      (node (ref "U102") (pin "5") (pinfunction "+IN_5") (pintype "input"))
    )
    (net (code "24") (name "LEDS_SCK") (class "Default")
      (node (ref "IC101") (pin "3") (pinfunction "SCLK_3") (pintype "bidirectional"))
      (node (ref "U101") (pin "26") (pinfunction "PB3_26") (pintype "bidirectional"))
    )
    (net (code "25") (name "LEDS_SIN") (class "Default")
      (node (ref "IC101") (pin "2") (pinfunction "SIN_2") (pintype "bidirectional"))
      (node (ref "U101") (pin "28") (pinfunction "PB5_28") (pintype "bidirectional"))
    )
    (net (code "26") (name "N_U") (class "Default")
      (node (ref "U100") (pin "6") (pinfunction "-IN_6") (pintype "input"))
      (node (ref "U100") (pin "7") (pinfunction "OUT_7") (pintype "output"))
    )
    (net (code "27") (name "Net-(C119-Pad2)") (class "Default")
      (node (ref "C119") (pin "2") (pinfunction "2_2") (pintype "passive"))
      (node (ref "Q103") (pin "1") (pinfunction "1_1") (pintype "passive"))
      (node (ref "R140") (pin "2") (pinfunction "2_2") (pintype "passive"))
    )
    (net (code "28") (name "Net-(C131-Pad1)") (class "Default")
      (node (ref "C131") (pin "1") (pinfunction "1_1") (pintype "passive"))
      (node (ref "D104") (pin "C") (pinfunction "C_C") (pintype "passive"))
      (node (ref "L102") (pin "1") (pinfunction "1_1") (pintype "passive"))
      (node (ref "L103") (pin "2") (pinfunction "2_2") (pintype "passive"))
      (node (ref "L104") (pin "2") (pinfunction "2_2") (pintype "passive"))
    )
    (net (code "29") (name "Net-(D100-PadC)") (class "Default")
      (node (ref "D100") (pin "C") (pinfunction "C_C") (pintype "passive"))
      (node (ref "Q100") (pin "B") (pinfunction "B_B") (pintype "passive"))
      (node (ref "R116") (pin "2") (pinfunction "2_2") (pintype "passive"))
      (node (ref "R117") (pin "2") (pinfunction "2_2") (pintype "passive"))
    )
    (net (code "30") (name "Net-(D101-PadC)") (class "Default")
      (node (ref "D101") (pin "C") (pinfunction "C_C") (pintype "passive"))
      (node (ref "Q101") (pin "B") (pinfunction "B_B") (pintype "passive"))
      (node (ref "R118") (pin "2") (pinfunction "2_2") (pintype "passive"))
      (node (ref "R122") (pin "2") (pinfunction "2_2") (pintype "passive"))
    )
    (net (code "31") (name "Net-(D102-PadC)") (class "Default")
      (node (ref "D102") (pin "C") (pinfunction "C_C") (pintype "passive"))
      (node (ref "Q102") (pin "B") (pinfunction "B_B") (pintype "passive"))
      (node (ref "R124") (pin "2") (pinfunction "2_2") (pintype "passive"))
      (node (ref "R127") (pin "2") (pinfunction "2_2") (pintype "passive"))
    )
    (net (code "32") (name "Net-(D103-PadA)") (class "Default")
      (node (ref "D103") (pin "A") (pinfunction "A_A") (pintype "passive"))
      (node (ref "L101") (pin "2") (pinfunction "2_2") (pintype "passive"))
    )
    (net (code "33") (name "Net-(IC1-VI)") (class "Default")
      (node (ref "C130") (pin "1") (pinfunction "1_1") (pintype "passive"))
      (node (ref "IC1") (pin "1") (pinfunction "VI_1") (pintype "input"))
      (node (ref "L102") (pin "2") (pinfunction "2_2") (pintype "passive"))
    )
    (net (code "34") (name "Net-(IC100A-+IN)") (class "Default")
      (node (ref "IC100") (pin "3") (pinfunction "+IN_3") (pintype "input"))
      (node (ref "R102") (pin "2") (pinfunction "2_2") (pintype "passive"))
      (node (ref "R103") (pin "1") (pinfunction "1_1") (pintype "passive"))
    )
    (net (code "35") (name "Net-(IC100A--IN)") (class "Default")
      (node (ref "IC100") (pin "2") (pinfunction "-IN_2") (pintype "input"))
      (node (ref "R133") (pin "1") (pinfunction "1_1") (pintype "passive"))
    )
    (net (code "36") (name "Net-(IC100A-OUT)") (class "Default")
      (node (ref "IC100") (pin "1") (pinfunction "OUT_1") (pintype "output"))
      (node (ref "R102") (pin "1") (pinfunction "1_1") (pintype "passive"))
      (node (ref "R108") (pin "2") (pinfunction "2_2") (pintype "passive"))
    )
    (net (code "37") (name "Net-(IC100B-+IN)") (class "Default")
      (node (ref "IC100") (pin "5") (pinfunction "+IN_5") (pintype "input"))
      (node (ref "R104") (pin "1") (pinfunction "1_1") (pintype "passive"))
      (node (ref "R105") (pin "2") (pinfunction "2_2") (pintype "passive"))
    )
    (net (code "38") (name "Net-(IC100B--IN)") (class "Default")
      (node (ref "IC100") (pin "6") (pinfunction "-IN_6") (pintype "input"))
      (node (ref "R134") (pin "1") (pinfunction "1_1") (pintype "passive"))
    )
    (net (code "39") (name "Net-(IC100B-OUT)") (class "Default")
      (node (ref "IC100") (pin "7") (pinfunction "OUT_7") (pintype "output"))
      (node (ref "R105") (pin "1") (pinfunction "1_1") (pintype "passive"))
      (node (ref "R109") (pin "2") (pinfunction "2_2") (pintype "passive"))
    )
    (net (code "40") (name "Net-(IC100C-+IN)") (class "Default")
      (node (ref "IC100") (pin "10") (pinfunction "+IN_10") (pintype "input"))
      (node (ref "R106") (pin "1") (pinfunction "1_1") (pintype "passive"))
      (node (ref "R110") (pin "2") (pinfunction "2_2") (pintype "passive"))
    )
    (net (code "41") (name "Net-(IC100C--IN)") (class "Default")
      (node (ref "IC100") (pin "9") (pinfunction "-IN_9") (pintype "input"))
      (node (ref "R135") (pin "1") (pinfunction "1_1") (pintype "passive"))
    )
    (net (code "42") (name "Net-(IC100C-OUT)") (class "Default")
      (node (ref "IC100") (pin "8") (pinfunction "OUT_8") (pintype "output"))
      (node (ref "R110") (pin "1") (pinfunction "1_1") (pintype "passive"))
      (node (ref "R113") (pin "2") (pinfunction "2_2") (pintype "passive"))
    )
    (net (code "43") (name "Net-(IC100D--IN)") (class "Default")
      (node (ref "IC100") (pin "13") (pinfunction "-IN_13") (pintype "input"))
      (node (ref "IC100") (pin "14") (pinfunction "OUT_14") (pintype "output"))
    )
    (net (code "44") (name "Net-(IC101-IREF)") (class "Default")
      (node (ref "IC101") (pin "23") (pinfunction "IREF_23") (pintype "bidirectional"))
      (node (ref "R142") (pin "1") (pinfunction "1_1") (pintype "passive"))
    )
    (net (code "45") (name "Net-(IC101-OUT1)") (class "Default")
      (node (ref "IC101") (pin "6") (pinfunction "OUT1_6") (pintype "bidirectional"))
      (node (ref "R131") (pin "2") (pinfunction "2_2") (pintype "passive"))
    )
    (net (code "46") (name "Net-(IC101-OUT2)") (class "Default")
      (node (ref "IC101") (pin "7") (pinfunction "OUT2_7") (pintype "bidirectional"))
      (node (ref "MODE_C") (pin "RED_C") (pinfunction "RED_RED_C") (pintype "bidirectional"))
    )
    (net (code "47") (name "Net-(IC101-OUT3)") (class "Default")
      (node (ref "IC101") (pin "8") (pinfunction "OUT3_8") (pintype "bidirectional"))
      (node (ref "MODE_C") (pin "GREEN_C") (pinfunction "GRN_GREEN_C") (pintype "bidirectional"))
    )
    (net (code "48") (name "Net-(IC101-OUT4)") (class "Default")
      (node (ref "IC101") (pin "9") (pinfunction "OUT4_9") (pintype "bidirectional"))
      (node (ref "MODE_A") (pin "GREEN_C") (pinfunction "GRN_GREEN_C") (pintype "bidirectional"))
    )
    (net (code "49") (name "Net-(IC101-OUT5)") (class "Default")
      (node (ref "IC101") (pin "10") (pinfunction "OUT5_10") (pintype "bidirectional"))
      (node (ref "MODE_A") (pin "RED_C") (pinfunction "RED_RED_C") (pintype "bidirectional"))
    )
    (net (code "50") (name "Net-(IC101-OUT6)") (class "Default")
      (node (ref "IC101") (pin "11") (pinfunction "OUT6_11") (pintype "bidirectional"))
      (node (ref "MODE_B") (pin "GREEN_C") (pinfunction "GRN_GREEN_C") (pintype "bidirectional"))
    )
    (net (code "51") (name "Net-(IC101-OUT7)") (class "Default")
      (node (ref "IC101") (pin "12") (pinfunction "OUT7_12") (pintype "bidirectional"))
      (node (ref "MODE_B") (pin "RED_C") (pinfunction "RED_RED_C") (pintype "bidirectional"))
    )
    (net (code "52") (name "Net-(IC101-OUT8)") (class "Default")
      (node (ref "IC101") (pin "13") (pinfunction "OUT8_13") (pintype "bidirectional"))
      (node (ref "LED1") (pin "GREEN_C") (pinfunction "GRN_GREEN_C") (pintype "bidirectional"))
    )
    (net (code "53") (name "Net-(IC101-OUT9)") (class "Default")
      (node (ref "IC101") (pin "14") (pinfunction "OUT9_14") (pintype "bidirectional"))
      (node (ref "LED1") (pin "RED_C") (pinfunction "RED_RED_C") (pintype "bidirectional"))
    )
    (net (code "54") (name "Net-(IC101-OUT10)") (class "Default")
      (node (ref "IC101") (pin "15") (pinfunction "OUT10_15") (pintype "bidirectional"))
      (node (ref "LED2") (pin "RED_C") (pinfunction "RED_RED_C") (pintype "bidirectional"))
    )
    (net (code "55") (name "Net-(IC101-OUT11)") (class "Default")
      (node (ref "IC101") (pin "16") (pinfunction "OUT11_16") (pintype "bidirectional"))
      (node (ref "LED2") (pin "GREEN_C") (pinfunction "GRN_GREEN_C") (pintype "bidirectional"))
    )
    (net (code "56") (name "Net-(IC101-OUT12)") (class "Default")
      (node (ref "IC101") (pin "17") (pinfunction "OUT12_17") (pintype "bidirectional"))
      (node (ref "LED3") (pin "RED_C") (pinfunction "RED_RED_C") (pintype "bidirectional"))
    )
    (net (code "57") (name "Net-(IC101-OUT13)") (class "Default")
      (node (ref "IC101") (pin "18") (pinfunction "OUT13_18") (pintype "bidirectional"))
      (node (ref "LED3") (pin "GREEN_C") (pinfunction "GRN_GREEN_C") (pintype "bidirectional"))
    )
    (net (code "58") (name "Net-(IC101-OUT14)") (class "Default")
      (node (ref "IC101") (pin "19") (pinfunction "OUT14_19") (pintype "bidirectional"))
      (node (ref "R136") (pin "2") (pinfunction "2_2") (pintype "passive"))
    )
    (net (code "59") (name "Net-(IC101-OUT15)") (class "Default")
      (node (ref "IC101") (pin "20") (pinfunction "OUT15_20") (pintype "bidirectional"))
      (node (ref "R132") (pin "2") (pinfunction "2_2") (pintype "passive"))
    )
    (net (code "60") (name "Net-(IC101-VCC)") (class "Default")
      (node (ref "C113") (pin "1") (pinfunction "1_1") (pintype "passive"))
      (node (ref "C114") (pin "1") (pinfunction "1_1") (pintype "passive"))
      (node (ref "IC101") (pin "24") (pinfunction "VCC_24") (pintype "bidirectional"))
      (node (ref "L100") (pin "1") (pinfunction "1_1") (pintype "passive"))
    )
    (net (code "61") (name "Net-(IC102A-X0)") (class "Default")
      (node (ref "IC102") (pin "13") (pinfunction "X0_13") (pintype "bidirectional"))
      (node (ref "POT_C") (pin "P$2") (pinfunction "S_P$2") (pintype "passive"))
    )
    (net (code "62") (name "Net-(IC102A-X1)") (class "Default")
      (node (ref "IC102") (pin "14") (pinfunction "X1_14") (pintype "bidirectional"))
      (node (ref "SLD_C") (pin "2") (pinfunction "S_2") (pintype "passive"))
    )
    (net (code "63") (name "Net-(IC102A-X2)") (class "Default")
      (node (ref "IC102") (pin "15") (pinfunction "X2_15") (pintype "bidirectional"))
      (node (ref "SLD_B") (pin "2") (pinfunction "S_2") (pintype "passive"))
    )
    (net (code "64") (name "Net-(IC102A-X3)") (class "Default")
      (node (ref "IC102") (pin "12") (pinfunction "X3_12") (pintype "bidirectional"))
      (node (ref "POT_A") (pin "P$2") (pinfunction "S_P$2") (pintype "passive"))
    )
    (net (code "65") (name "Net-(IC102A-X4)") (class "Default")
      (node (ref "IC102") (pin "1") (pinfunction "X4_1") (pintype "bidirectional"))
      (node (ref "SLD_A") (pin "2") (pinfunction "S_2") (pintype "passive"))
    )
    (net (code "66") (name "Net-(IC102A-X6)") (class "Default")
      (node (ref "IC102") (pin "2") (pinfunction "X6_2") (pintype "bidirectional"))
      (node (ref "POT_B") (pin "P$2") (pinfunction "S_P$2") (pintype "passive"))
    )
    (net (code "67") (name "Net-(IC104-VI)") (class "Default")
      (node (ref "C132") (pin "1") (pinfunction "1_1") (pintype "passive"))
      (node (ref "IC104") (pin "3") (pinfunction "VI_3") (pintype "input"))
      (node (ref "L103") (pin "1") (pinfunction "1_1") (pintype "passive"))
    )
    (net (code "68") (name "Net-(J2-3)") (class "Default")
      (node (ref "J2") (pin "P3") (pinfunction "3_P3") (pintype "passive"))
      (node (ref "R128") (pin "2") (pinfunction "2_2") (pintype "passive"))
    )
    (net (code "69") (name "Net-(J6-3)") (class "Default")
      (node (ref "J6") (pin "P3") (pinfunction "3_P3") (pintype "passive"))
      (node (ref "R115") (pin "2") (pinfunction "2_2") (pintype "passive"))
    )
    (net (code "70") (name "Net-(J7-3)") (class "Default")
      (node (ref "J7") (pin "P3") (pinfunction "3_P3") (pintype "passive"))
      (node (ref "R113") (pin "1") (pinfunction "1_1") (pintype "passive"))
    )
    (net (code "71") (name "Net-(J8-3)") (class "Default")
      (node (ref "J8") (pin "P3") (pinfunction "3_P3") (pintype "passive"))
      (node (ref "R109") (pin "1") (pinfunction "1_1") (pintype "passive"))
    )
    (net (code "72") (name "Net-(J9-3)") (class "Default")
      (node (ref "J9") (pin "P3") (pinfunction "3_P3") (pintype "passive"))
      (node (ref "R108") (pin "1") (pinfunction "1_1") (pintype "passive"))
    )
    (net (code "73") (name "Net-(J10-3)") (class "Default")
      (node (ref "J10") (pin "P3") (pinfunction "3_P3") (pintype "passive"))
      (node (ref "R107") (pin "1") (pinfunction "1_1") (pintype "passive"))
      (node (ref "R111") (pin "1") (pinfunction "1_1") (pintype "passive"))
    )
    (net (code "74") (name "Net-(J11-3)") (class "Default")
      (node (ref "J11") (pin "P3") (pinfunction "3_P3") (pintype "passive"))
      (node (ref "R101") (pin "1") (pinfunction "1_1") (pintype "passive"))
      (node (ref "R125") (pin "1") (pinfunction "1_1") (pintype "passive"))
    )
    (net (code "75") (name "Net-(J12-3)") (class "Default")
      (node (ref "J12") (pin "P3") (pinfunction "3_P3") (pintype "passive"))
      (node (ref "R100") (pin "1") (pinfunction "1_1") (pintype "passive"))
      (node (ref "R119") (pin "1") (pinfunction "1_1") (pintype "passive"))
    )
    (net (code "76") (name "Net-(Q103B-2)") (class "Default")
      (node (ref "C120") (pin "2") (pinfunction "2_2") (pintype "passive"))
      (node (ref "Q103") (pin "3") (pinfunction "2_3") (pintype "passive"))
      (node (ref "R141") (pin "2") (pinfunction "2_2") (pintype "passive"))
    )
    (net (code "77") (name "Net-(SLD_AA-C)") (class "Default")
      (node (ref "R136") (pin "1") (pinfunction "1_1") (pintype "passive"))
      (node (ref "SLD_A") (pin "E") (pinfunction "C_E") (pintype "passive"))
    )
    (net (code "78") (name "Net-(SLD_BA-C)") (class "Default")
      (node (ref "R132") (pin "1") (pinfunction "1_1") (pintype "passive"))
      (node (ref "SLD_B") (pin "E") (pinfunction "C_E") (pintype "passive"))
    )
    (net (code "79") (name "Net-(SLD_CA-C)") (class "Default")
      (node (ref "R131") (pin "1") (pinfunction "1_1") (pintype "passive"))
      (node (ref "SLD_C") (pin "E") (pinfunction "C_E") (pintype "passive"))
    )
    (net (code "80") (name "Net-(U100A--IN)") (class "Default")
      (node (ref "C104") (pin "1") (pinfunction "1_1") (pintype "passive"))
      (node (ref "R115") (pin "1") (pinfunction "1_1") (pintype "passive"))
      (node (ref "R130") (pin "2") (pinfunction "2_2") (pintype "passive"))
      (node (ref "R145") (pin "1") (pinfunction "1_1") (pintype "passive"))
      (node (ref "U100") (pin "2") (pinfunction "-IN_2") (pintype "input"))
    )
    (net (code "81") (name "Net-(U100C--IN)") (class "Default")
      (node (ref "C108") (pin "1") (pinfunction "1_1") (pintype "passive"))
      (node (ref "R121") (pin "1") (pinfunction "1_1") (pintype "passive"))
      (node (ref "R138") (pin "2") (pinfunction "2_2") (pintype "passive"))
      (node (ref "R144") (pin "1") (pinfunction "1_1") (pintype "passive"))
      (node (ref "U100") (pin "9") (pinfunction "-IN_9") (pintype "input"))
    )
    (net (code "82") (name "Net-(U100D--IN)") (class "Default")
      (node (ref "C107") (pin "1") (pinfunction "1_1") (pintype "passive"))
      (node (ref "R128") (pin "1") (pinfunction "1_1") (pintype "passive"))
      (node (ref "R137") (pin "2") (pinfunction "2_2") (pintype "passive"))
      (node (ref "R143") (pin "1") (pinfunction "1_1") (pintype "passive"))
      (node (ref "U100") (pin "13") (pinfunction "-IN_13") (pintype "input"))
    )
    (net (code "83") (name "Net-(U101-PF0{slash}OSC_IN)") (class "Default")
      (node (ref "R141") (pin "1") (pinfunction "1_1") (pintype "passive"))
      (node (ref "U101") (pin "2") (pinfunction "PF0/OSC_IN_2") (pintype "bidirectional"))
    )
    (net (code "84") (name "Net-(U101-PF1{slash}OSC_OUT)") (class "Default")
      (node (ref "R140") (pin "1") (pinfunction "1_1") (pintype "passive"))
      (node (ref "U101") (pin "3") (pinfunction "PF1/OSC_OUT_3") (pintype "bidirectional"))
    )
    (net (code "85") (name "Net-(U102A--IN)") (class "Default")
      (node (ref "C102") (pin "1") (pinfunction "1_1") (pintype "passive"))
      (node (ref "R119") (pin "2") (pinfunction "2_2") (pintype "passive"))
      (node (ref "R120") (pin "1") (pinfunction "1_1") (pintype "passive"))
      (node (ref "R123") (pin "1") (pinfunction "1_1") (pintype "passive"))
      (node (ref "U102") (pin "2") (pinfunction "-IN_2") (pintype "input"))
    )
    (net (code "86") (name "Net-(U102A-OUT)") (class "Default")
      (node (ref "C102") (pin "2") (pinfunction "2_2") (pintype "passive"))
      (node (ref "R100") (pin "2") (pinfunction "2_2") (pintype "passive"))
      (node (ref "U102") (pin "1") (pinfunction "OUT_1") (pintype "output"))
    )
    (net (code "87") (name "Net-(U102B--IN)") (class "Default")
      (node (ref "C103") (pin "1") (pinfunction "1_1") (pintype "passive"))
      (node (ref "R125") (pin "2") (pinfunction "2_2") (pintype "passive"))
      (node (ref "R126") (pin "1") (pinfunction "1_1") (pintype "passive"))
      (node (ref "R129") (pin "1") (pinfunction "1_1") (pintype "passive"))
      (node (ref "U102") (pin "6") (pinfunction "-IN_6") (pintype "input"))
    )
    (net (code "88") (name "Net-(U102B-OUT)") (class "Default")
      (node (ref "C103") (pin "2") (pinfunction "2_2") (pintype "passive"))
      (node (ref "R101") (pin "2") (pinfunction "2_2") (pintype "passive"))
      (node (ref "U102") (pin "7") (pinfunction "OUT_7") (pintype "output"))
    )
    (net (code "89") (name "Net-(U102C--IN)") (class "Default")
      (node (ref "C101") (pin "1") (pinfunction "1_1") (pintype "passive"))
      (node (ref "R111") (pin "2") (pinfunction "2_2") (pintype "passive"))
      (node (ref "R112") (pin "1") (pinfunction "1_1") (pintype "passive"))
      (node (ref "R114") (pin "1") (pinfunction "1_1") (pintype "passive"))
      (node (ref "U102") (pin "9") (pinfunction "-IN_9") (pintype "input"))
    )
    (net (code "90") (name "Net-(U102C-OUT)") (class "Default")
      (node (ref "C101") (pin "2") (pinfunction "2_2") (pintype "passive"))
      (node (ref "R107") (pin "2") (pinfunction "2_2") (pintype "passive"))
      (node (ref "U102") (pin "8") (pinfunction "OUT_8") (pintype "output"))
    )
    (net (code "91") (name "Net-(U102D--IN)") (class "Default")
      (node (ref "U102") (pin "13") (pinfunction "-IN_13") (pintype "input"))
      (node (ref "U102") (pin "14") (pinfunction "OUT_14") (pintype "output"))
    )
    (net (code "92") (name "POTS_ADDR_A") (class "Default")
      (node (ref "IC102") (pin "11") (pinfunction "A_11") (pintype "input"))
      (node (ref "U101") (pin "13") (pinfunction "PA7_13") (pintype "bidirectional"))
    )
    (net (code "93") (name "POTS_ADDR_B") (class "Default")
      (node (ref "IC102") (pin "10") (pinfunction "B_10") (pintype "input"))
      (node (ref "U101") (pin "18") (pinfunction "PA8_18") (pintype "bidirectional"))
    )
    (net (code "94") (name "POTS_ADDR_C") (class "Default")
      (node (ref "IC102") (pin "9") (pinfunction "C_9") (pintype "input"))
      (node (ref "U101") (pin "19") (pinfunction "PA9_19") (pintype "bidirectional"))
    )
    (net (code "95") (name "RESET") (class "Default")
      (node (ref "C109") (pin "1") (pinfunction "1_1") (pintype "passive"))
      (node (ref "JP100") (pin "4") (pinfunction "4_4") (pintype "passive"))
      (node (ref "R139") (pin "2") (pinfunction "2_2") (pintype "passive"))
      (node (ref "U101") (pin "4") (pinfunction "NRST_4") (pintype "bidirectional"))
    )
    (net (code "96") (name "SWCLK") (class "Default")
      (node (ref "JP100") (pin "3") (pinfunction "3_3") (pintype "passive"))
      (node (ref "U101") (pin "24") (pinfunction "PA14_24") (pintype "bidirectional"))
    )
    (net (code "97") (name "SWDIO") (class "Default")
      (node (ref "JP100") (pin "2") (pinfunction "2_2") (pintype "passive"))
      (node (ref "U101") (pin "23") (pinfunction "PA13_23") (pintype "bidirectional"))
    )
    (net (code "98") (name "SW_MODE_A") (class "Default")
      (node (ref "SW_A") (pin "3") (pinfunction "3_3") (pintype "passive"))
      (node (ref "SW_A") (pin "4") (pinfunction "4_4") (pintype "passive"))
      (node (ref "U101") (pin "27") (pinfunction "PB4_27") (pintype "bidirectional"))
    )
    (net (code "99") (name "SW_MODE_B") (class "Default")
      (node (ref "SW_B") (pin "3") (pinfunction "3_3") (pintype "passive"))
      (node (ref "SW_B") (pin "4") (pinfunction "4_4") (pintype "passive"))
      (node (ref "U101") (pin "29") (pinfunction "PB6_29") (pintype "bidirectional"))
    )
    (net (code "100") (name "SW_MODE_C") (class "Default")
      (node (ref "SW_C") (pin "3") (pinfunction "3_3") (pintype "passive"))
      (node (ref "SW_C") (pin "4") (pinfunction "4_4") (pintype "passive"))
      (node (ref "U101") (pin "30") (pinfunction "PB7_30") (pintype "bidirectional"))
    )
    (net (code "101") (name "VCC") (class "Default")
      (node (ref "C100") (pin "1") (pinfunction "1_1") (pintype "passive"))
      (node (ref "C106") (pin "1") (pinfunction "1_1") (pintype "passive"))
      (node (ref "C133") (pin "1") (pinfunction "1_1") (pintype "passive"))
      (node (ref "C134") (pin "1") (pinfunction "1_1") (pintype "passive"))
      (node (ref "IC100") (pin "4") (pinfunction "V+_4") (pintype "power_in"))
      (node (ref "L104") (pin "1") (pinfunction "1_1") (pintype "passive"))
      (node (ref "U$1") (pin "1") (pinfunction "P$1_1") (pintype "bidirectional"))
      (node (ref "U102") (pin "4") (pinfunction "V+_4") (pintype "power_in"))
    )
    (net (code "102") (name "VEE") (class "Default")
      (node (ref "C112") (pin "2") (pinfunction "2_2") (pintype "passive"))
      (node (ref "C128") (pin "2") (pinfunction "2_2") (pintype "passive"))
      (node (ref "C129") (pin "2") (pinfunction "2_2") (pintype "passive"))
      (node (ref "L101") (pin "1") (pinfunction "1_1") (pintype "passive"))
      (node (ref "R146") (pin "1") (pinfunction "1_1") (pintype "passive"))
      (node (ref "U$1") (pin "2") (pinfunction "P$2_2") (pintype "bidirectional"))
      (node (ref "U102") (pin "11") (pinfunction "V-_11") (pintype "power_in"))
    )
    (net (code "103") (name "unconnected-(IC101-LAT-Pad4)") (class "Default")
      (node (ref "IC101") (pin "4") (pinfunction "LAT_4") (pintype "bidirectional"))
    )
    (net (code "104") (name "unconnected-(IC101-OUT0-Pad5)") (class "Default")
      (node (ref "IC101") (pin "5") (pinfunction "OUT0_5") (pintype "bidirectional"))
    )
    (net (code "105") (name "unconnected-(IC101-SOUT-Pad22)") (class "Default")
      (node (ref "IC101") (pin "22") (pinfunction "SOUT_22") (pintype "bidirectional"))
    )
    (net (code "106") (name "unconnected-(IC102A-X5-Pad5)") (class "Default")
      (node (ref "IC102") (pin "5") (pinfunction "X5_5") (pintype "bidirectional"))
    )
    (net (code "107") (name "unconnected-(IC102A-X7-Pad4)") (class "Default")
      (node (ref "IC102") (pin "4") (pinfunction "X7_4") (pintype "bidirectional"))
    )
    (net (code "108") (name "unconnected-(J7-2-PadP2)") (class "Default")
      (node (ref "J7") (pin "P2") (pinfunction "2_P2") (pintype "passive"))
    )
    (net (code "109") (name "unconnected-(J8-2-PadP2)") (class "Default")
      (node (ref "J8") (pin "P2") (pinfunction "2_P2") (pintype "passive"))
    )
    (net (code "110") (name "unconnected-(J9-2-PadP2)") (class "Default")
      (node (ref "J9") (pin "P2") (pinfunction "2_P2") (pintype "passive"))
    )
    (net (code "111") (name "unconnected-(J10-2-PadP2)") (class "Default")
      (node (ref "J10") (pin "P2") (pinfunction "2_P2") (pintype "passive"))
    )
    (net (code "112") (name "unconnected-(J11-2-PadP2)") (class "Default")
      (node (ref "J11") (pin "P2") (pinfunction "2_P2") (pintype "passive"))
    )
    (net (code "113") (name "unconnected-(J12-2-PadP2)") (class "Default")
      (node (ref "J12") (pin "P2") (pinfunction "2_P2") (pintype "passive"))
    )
  )
)
